# Sheet1.net
KiCad netlist of a schematic drawn in Altium Designer
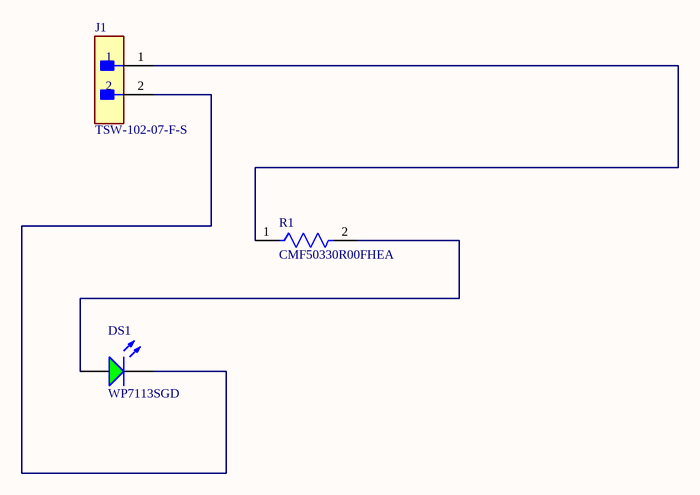
[diagram p0: Sheet1.SchDoc]

(export (version "E")
  (design (tool "Eeschema 10.0.6"))
  (components
    (comp (ref "DS1")
      (value "WP7113SGD")
      (footprint "KING-WP7113SGD_V")
      (description "LED Green, 62.5 mW, 25 mA, -40 to 85 degC, 2-Pin THD, RoHS, Bulk")
      (fields (field (name "MANUFACTURER") "Kingbright"))
      (libsource (lib "Altium Content Vault") (part "LED-GREEN-AK-2"))
    )
    (comp (ref "J1")
      (value "TSW-102-07-F-S")
      (footprint "FP-TSW-102-07-F-S-MFG")
      (description "CONN HEADER VERT 2POS 2.54MM")
      (libsource (lib "Altium Content Vault") (part "3bc925449376181038e59eaffc5286c"))
    )
    (comp (ref "R1")
      (value "CMF50330R00FHEA")
      (footprint "FP-CMF50-0")
      (description "CMF50330R00FHEA Res Mtlflm CMF-50 330 Ohm 1% T-2 Ea E3 Axl Th")
      (fields (field (name "TOLERANCE") "1%"))
      (libsource (lib "Altium Content Vault") (part "1029c3af85768c4190bb7ad29bc67b5"))
    )
  )
  (nets
    (net (code "1") (name "Net-(DS1-A)") (class "Default")
      (node (ref "DS1") (pin "1") (pinfunction "A_1") (pintype "passive"))
      (node (ref "R1") (pin "2") (pinfunction "2_2") (pintype "passive"))
    )
    (net (code "2") (name "Net-(DS1-K)") (class "Default")
      (node (ref "DS1") (pin "2") (pinfunction "K_2") (pintype "passive"))
      (node (ref "J1") (pin "2") (pinfunction "2_2") (pintype "passive"))
    )
    (net (code "3") (name "Net-(J1-Pad1)") (class "Default")
      (node (ref "J1") (pin "1") (pinfunction "1_1") (pintype "passive"))
      (node (ref "R1") (pin "1") (pinfunction "1_1") (pintype "passive"))
    )
  )
)
